# sch_USB3_0.net
KiCad netlist of a schematic drawn in Altium Designer
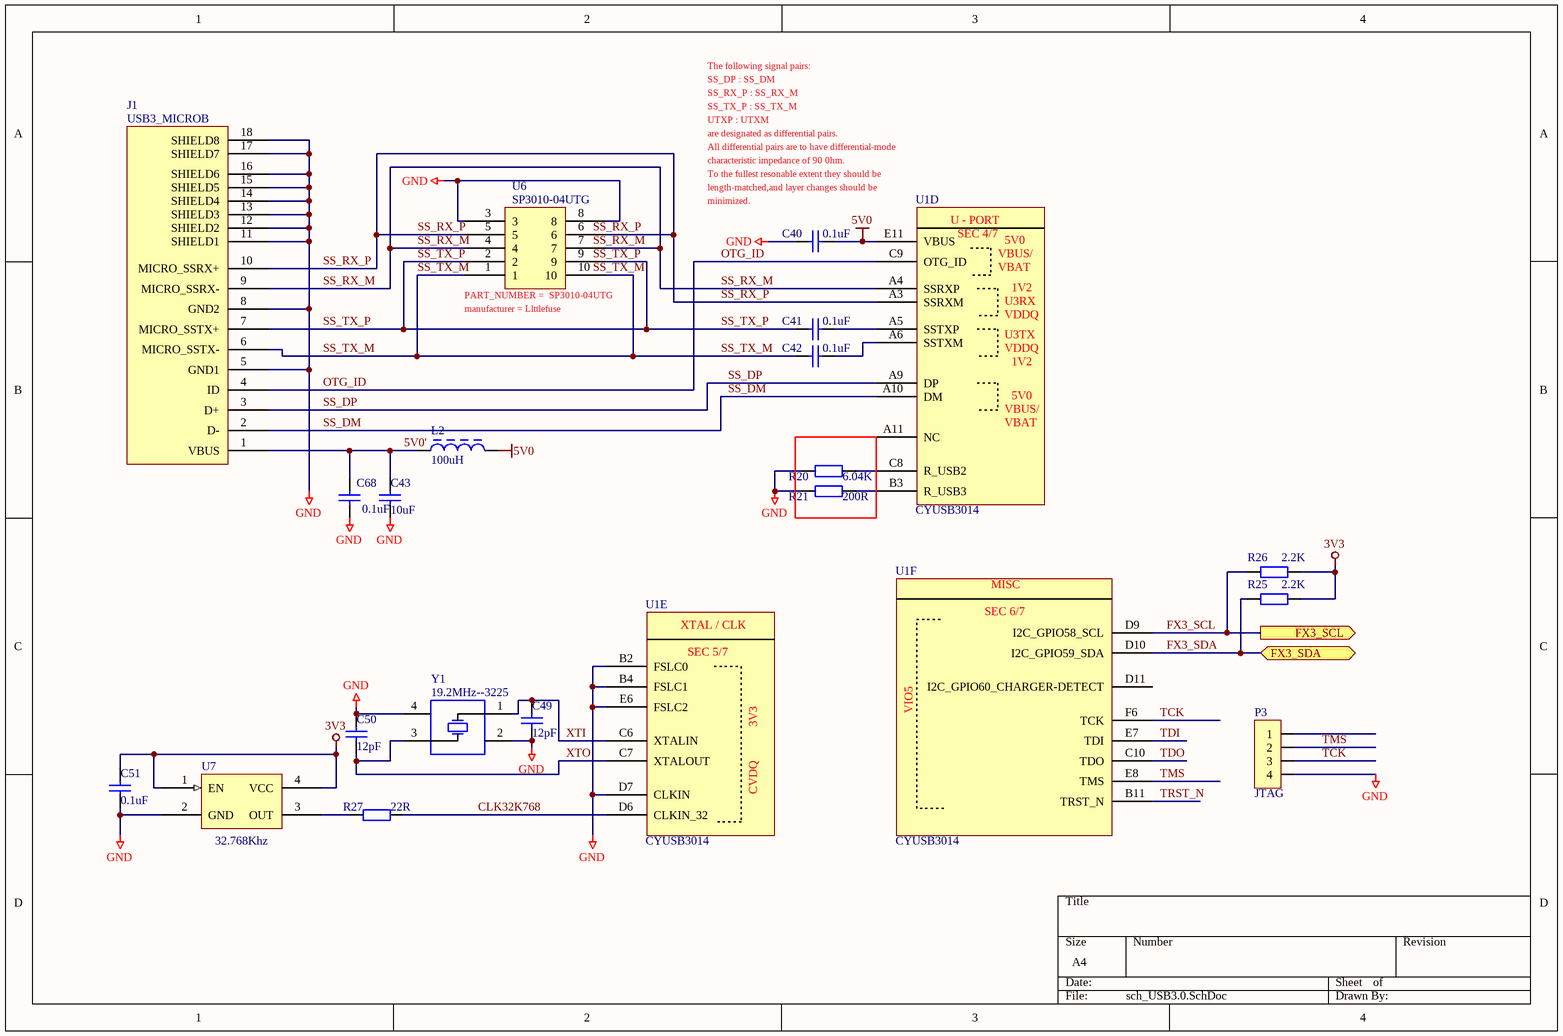
[diagram p0: sch_USB3.0.SchDoc]

(export (version "E")
  (design (tool "Eeschema 10.0.6"))
  (components
    (comp (ref "C40")
      (value "0.1uF")
      (footprint "0402C")
      (description "Capacitor")
      (fields (field (name "PUBLISHER") "Altium Limited"))
      (libsource (lib "Miscellaneous Devices") (part "Cap"))
    )
    (comp (ref "C41")
      (value "0.1uF")
      (footprint "0402C")
      (description "Capacitor")
      (fields (field (name "PUBLISHER") "Altium Limited"))
      (libsource (lib "Miscellaneous Devices") (part "Cap"))
    )
    (comp (ref "C42")
      (value "0.1uF")
      (footprint "0402C")
      (description "Capacitor")
      (fields (field (name "PUBLISHER") "Altium Limited"))
      (libsource (lib "Miscellaneous Devices") (part "Cap"))
    )
    (comp (ref "C43")
      (value "10uF")
      (footprint "0805C")
      (description "Capacitor")
      (fields (field (name "PUBLISHER") "Altium Limited"))
      (libsource (lib "Miscellaneous Devices") (part "Cap"))
    )
    (comp (ref "C49")
      (value "12pF")
      (footprint "0402C")
      (description "Capacitor")
      (fields (field (name "PUBLISHER") "Altium Limited"))
      (libsource (lib "Miscellaneous Devices") (part "Cap"))
    )
    (comp (ref "C50")
      (value "12pF")
      (footprint "0402C")
      (description "Capacitor")
      (fields (field (name "PUBLISHER") "Altium Limited"))
      (libsource (lib "Miscellaneous Devices") (part "Cap"))
    )
    (comp (ref "C51")
      (value "0.1uF")
      (footprint "0402C")
      (description "Capacitor")
      (fields (field (name "PUBLISHER") "Altium Limited"))
      (libsource (lib "Miscellaneous Devices") (part "Cap"))
    )
    (comp (ref "C68")
      (value "0.1uF")
      (footprint "0402C")
      (description "Capacitor")
      (fields (field (name "PUBLISHER") "Altium Limited"))
      (libsource (lib "Miscellaneous Devices") (part "Cap"))
    )
    (comp (ref "J1")
      (value "USB3_MICROB")
      (footprint "USB3_BA_P65L130W51H28")
      (libsource (lib "SZG") (part "USB3_MICROB"))
    )
    (comp (ref "L2")
      (value "100uH")
      (footprint "L_P3D6H9")
      (description "7.2.04.0034 立式电感受10uH 2A")
      (libsource (lib "*") (part "L"))
    )
    (comp (ref "P3")
      (value "JTAG")
      (footprint "WAFER4_P1.25L6.25W3.4H4.3")
      (libsource (lib "KS_Drive") (part "CON4"))
    )
    (comp (ref "R20")
      (value "6.04K")
      (footprint "0402R")
      (description "Resistor")
      (fields (field (name "PUBLISHER") "Altium Limited"))
      (libsource (lib "SZG") (part "Resistor"))
    )
    (comp (ref "R21")
      (value "200R")
      (footprint "0402R")
      (description "Resistor")
      (fields (field (name "PUBLISHER") "Altium Limited"))
      (libsource (lib "SZG") (part "Resistor"))
    )
    (comp (ref "R25")
      (value "2.2K")
      (footprint "0402R")
      (description "Resistor")
      (fields (field (name "PUBLISHER") "Altium Limited"))
      (libsource (lib "SZG") (part "Resistor"))
    )
    (comp (ref "R26")
      (value "2.2K")
      (footprint "0402R")
      (description "Resistor")
      (fields (field (name "PUBLISHER") "Altium Limited"))
      (libsource (lib "SZG") (part "Resistor"))
    )
    (comp (ref "R27")
      (value "22R")
      (footprint "0402R")
      (description "Resistor")
      (fields (field (name "PUBLISHER") "Altium Limited"))
      (libsource (lib "SZG") (part "Resistor"))
    )
    (comp (ref "U1")
      (value "CYUSB3014")
      (footprint "FBGA121_P80L100W100H11")
      (libsource (lib "TXW") (part "CYUSB3014"))
    )
    (comp (ref "U6")
      (value "SP3010-04UTG")
      (footprint "UDFN10_SON_P50L25W10H55")
      (libsource (lib "SZG") (part "SP3010-04UTG"))
    )
    (comp (ref "U7")
      (value "XTAL-3225")
      (footprint "XTAL_3225")
      (libsource (lib "常用晶振器件图SCH") (part "XTAL."))
    )
    (comp (ref "Y1")
      (value "19.2MHz--3225")
      (footprint "XTAL_3225")
      (description "Crystal Oscillator")
      (libsource (lib "常用晶振器件图SCH") (part "XTAL"))
    )
  )
  (nets
    (net (code "1") (name "/5V0'") (class "Default")
      (node (ref "C43") (pin "2") (pinfunction "2_2") (pintype "passive"))
      (node (ref "C68") (pin "1") (pinfunction "1_1") (pintype "passive"))
      (node (ref "J1") (pin "1") (pinfunction "VBUS_1") (pintype "power_in"))
      (node (ref "L2") (pin "1") (pintype "passive"))
    )
    (net (code "2") (name "/CLK32K768") (class "Default")
      (node (ref "R27") (pin "1") (pinfunction "1_1") (pintype "passive"))
      (node (ref "U1") (pin "D6") (pinfunction "CLKIN_32_D6") (pintype "passive"))
    )
    (net (code "3") (name "/FX3_SCL") (class "Default")
      (node (ref "R26") (pin "2") (pinfunction "2_2") (pintype "passive"))
      (node (ref "U1") (pin "D9") (pinfunction "I2C_GPIO58_SCL_D9") (pintype "passive"))
    )
    (net (code "4") (name "/FX3_SDA") (class "Default")
      (node (ref "R25") (pin "2") (pinfunction "2_2") (pintype "passive"))
      (node (ref "U1") (pin "D10") (pinfunction "I2C_GPIO59_SDA_D10") (pintype "passive"))
    )
    (net (code "5") (name "/OTG_ID") (class "Default")
      (node (ref "J1") (pin "4") (pinfunction "ID_4") (pintype "power_in"))
      (node (ref "U1") (pin "C9") (pinfunction "OTG_ID_C9") (pintype "power_in"))
    )
    (net (code "6") (name "/SS_DM") (class "Default")
      (node (ref "J1") (pin "2") (pinfunction "D-_2") (pintype "power_in"))
      (node (ref "U1") (pin "A10") (pinfunction "DM_A10") (pintype "power_in"))
    )
    (net (code "7") (name "/SS_DP") (class "Default")
      (node (ref "J1") (pin "3") (pinfunction "D+_3") (pintype "power_in"))
      (node (ref "U1") (pin "A9") (pinfunction "DP_A9") (pintype "power_in"))
    )
    (net (code "8") (name "/SS_RX_M") (class "Default")
      (node (ref "J1") (pin "9") (pinfunction "MICRO_SSRX-_9") (pintype "power_in"))
      (node (ref "U1") (pin "A4") (pinfunction "SSRXP_A4") (pintype "power_in"))
      (node (ref "U6") (pin "4") (pinfunction "4_4") (pintype "passive"))
      (node (ref "U6") (pin "7") (pinfunction "7_7") (pintype "passive"))
    )
    (net (code "9") (name "/SS_RX_P") (class "Default")
      (node (ref "J1") (pin "10") (pinfunction "MICRO_SSRX+_10") (pintype "power_in"))
      (node (ref "U1") (pin "A3") (pinfunction "SSRXM_A3") (pintype "power_in"))
      (node (ref "U6") (pin "5") (pinfunction "5_5") (pintype "passive"))
      (node (ref "U6") (pin "6") (pinfunction "6_6") (pintype "passive"))
    )
    (net (code "10") (name "/SS_TX_M") (class "Default")
      (node (ref "C42") (pin "2") (pinfunction "2_2") (pintype "passive"))
      (node (ref "J1") (pin "6") (pinfunction "MICRO_SSTX-_6") (pintype "power_in"))
      (node (ref "U6") (pin "1") (pinfunction "1_1") (pintype "passive"))
      (node (ref "U6") (pin "10") (pinfunction "10_10") (pintype "passive"))
    )
    (net (code "11") (name "/SS_TX_P") (class "Default")
      (node (ref "C41") (pin "2") (pinfunction "2_2") (pintype "passive"))
      (node (ref "J1") (pin "7") (pinfunction "MICRO_SSTX+_7") (pintype "power_in"))
      (node (ref "U6") (pin "2") (pinfunction "2_2") (pintype "passive"))
      (node (ref "U6") (pin "9") (pinfunction "9_9") (pintype "passive"))
    )
    (net (code "12") (name "/TCK") (class "Default")
      (node (ref "P3") (pin "3") (pinfunction "3_3") (pintype "passive"))
      (node (ref "U1") (pin "F6") (pinfunction "TCK_F6") (pintype "passive"))
    )
    (net (code "13") (name "/TDI") (class "Default")
      (node (ref "U1") (pin "E7") (pinfunction "TDI_E7") (pintype "passive"))
    )
    (net (code "14") (name "/TDO") (class "Default")
      (node (ref "U1") (pin "C10") (pinfunction "TDO_C10") (pintype "passive"))
    )
    (net (code "15") (name "/TMS") (class "Default")
      (node (ref "P3") (pin "2") (pinfunction "2_2") (pintype "passive"))
      (node (ref "U1") (pin "E8") (pinfunction "TMS_E8") (pintype "passive"))
    )
    (net (code "16") (name "/TRST_N") (class "Default")
      (node (ref "U1") (pin "B11") (pinfunction "TRST_N_B11") (pintype "passive"))
    )
    (net (code "17") (name "/XTI") (class "Default")
      (node (ref "C49") (pin "2") (pinfunction "2_2") (pintype "passive"))
      (node (ref "U1") (pin "C6") (pinfunction "XTALIN_C6") (pintype "passive"))
      (node (ref "Y1") (pin "1") (pinfunction "1_1") (pintype "passive"))
    )
    (net (code "18") (name "/XTO") (class "Default")
      (node (ref "C50") (pin "1") (pinfunction "1_1") (pintype "passive"))
      (node (ref "U1") (pin "C7") (pinfunction "XTALOUT_C7") (pintype "passive"))
      (node (ref "Y1") (pin "3") (pinfunction "3_3") (pintype "passive"))
    )
    (net (code "19") (name "3V3") (class "Default")
      (node (ref "C51") (pin "2") (pinfunction "2_2") (pintype "passive"))
      (node (ref "R25") (pin "1") (pinfunction "1_1") (pintype "passive"))
      (node (ref "R26") (pin "1") (pinfunction "1_1") (pintype "passive"))
      (node (ref "U7") (pin "1") (pinfunction "EN_1") (pintype "input"))
      (node (ref "U7") (pin "4") (pinfunction "VCC_4") (pintype "passive"))
    )
    (net (code "20") (name "5V0") (class "Default")
      (node (ref "C40") (pin "1") (pinfunction "1_1") (pintype "passive"))
      (node (ref "L2") (pin "2") (pintype "passive"))
      (node (ref "U1") (pin "E11") (pinfunction "VBUS_E11") (pintype "power_in"))
    )
    (net (code "21") (name "GND") (class "Default")
      (node (ref "C40") (pin "2") (pinfunction "2_2") (pintype "passive"))
      (node (ref "C43") (pin "1") (pinfunction "1_1") (pintype "passive"))
      (node (ref "C49") (pin "1") (pinfunction "1_1") (pintype "passive"))
      (node (ref "C50") (pin "2") (pinfunction "2_2") (pintype "passive"))
      (node (ref "C51") (pin "1") (pinfunction "1_1") (pintype "passive"))
      (node (ref "C68") (pin "2") (pinfunction "2_2") (pintype "passive"))
      (node (ref "J1") (pin "11") (pinfunction "SHIELD1_11") (pintype "power_in"))
      (node (ref "J1") (pin "12") (pinfunction "SHIELD2_12") (pintype "power_in"))
      (node (ref "J1") (pin "13") (pinfunction "SHIELD3_13") (pintype "power_in"))
      (node (ref "J1") (pin "14") (pinfunction "SHIELD4_14") (pintype "power_in"))
      (node (ref "J1") (pin "15") (pinfunction "SHIELD5_15") (pintype "power_in"))
      (node (ref "J1") (pin "16") (pinfunction "SHIELD6_16") (pintype "power_in"))
      (node (ref "J1") (pin "17") (pinfunction "SHIELD7_17") (pintype "power_in"))
      (node (ref "J1") (pin "18") (pinfunction "SHIELD8_18") (pintype "power_in"))
      (node (ref "J1") (pin "5") (pinfunction "GND1_5") (pintype "power_in"))
      (node (ref "J1") (pin "8") (pinfunction "GND2_8") (pintype "power_in"))
      (node (ref "P3") (pin "4") (pinfunction "4_4") (pintype "passive"))
      (node (ref "R20") (pin "2") (pinfunction "2_2") (pintype "passive"))
      (node (ref "R21") (pin "2") (pinfunction "2_2") (pintype "passive"))
      (node (ref "U1") (pin "B2") (pinfunction "FSLC0_B2") (pintype "passive"))
      (node (ref "U1") (pin "B4") (pinfunction "FSLC1_B4") (pintype "passive"))
      (node (ref "U1") (pin "D7") (pinfunction "CLKIN_D7") (pintype "passive"))
      (node (ref "U1") (pin "E6") (pinfunction "FSLC2_E6") (pintype "passive"))
      (node (ref "U6") (pin "3") (pinfunction "3_3") (pintype "passive"))
      (node (ref "U6") (pin "8") (pinfunction "8_8") (pintype "passive"))
      (node (ref "U7") (pin "2") (pinfunction "GND_2") (pintype "passive"))
      (node (ref "Y1") (pin "2") (pinfunction "2_2") (pintype "passive"))
      (node (ref "Y1") (pin "4") (pinfunction "4_4") (pintype "passive"))
    )
    (net (code "22") (name "Net-(U1D-R_USB2)") (class "Default")
      (node (ref "R20") (pin "1") (pinfunction "1_1") (pintype "passive"))
      (node (ref "U1") (pin "C8") (pinfunction "R_USB2_C8") (pintype "power_in"))
    )
    (net (code "23") (name "Net-(U1D-R_USB3)") (class "Default")
      (node (ref "R21") (pin "1") (pinfunction "1_1") (pintype "passive"))
      (node (ref "U1") (pin "B3") (pinfunction "R_USB3_B3") (pintype "power_in"))
    )
    (net (code "24") (name "Net-(U1D-SSTXM)") (class "Default")
      (node (ref "C42") (pin "1") (pinfunction "1_1") (pintype "passive"))
      (node (ref "U1") (pin "A6") (pinfunction "SSTXM_A6") (pintype "power_in"))
    )
    (net (code "25") (name "Net-(U1D-SSTXP)") (class "Default")
      (node (ref "C41") (pin "1") (pinfunction "1_1") (pintype "passive"))
      (node (ref "U1") (pin "A5") (pinfunction "SSTXP_A5") (pintype "power_in"))
    )
    (net (code "26") (name "Net-(U7-OUT)") (class "Default")
      (node (ref "R27") (pin "2") (pinfunction "2_2") (pintype "passive"))
      (node (ref "U7") (pin "3") (pinfunction "OUT_3") (pintype "passive"))
    )
    (net (code "27") (name "unconnected-(P3-Pad1)") (class "Default")
      (node (ref "P3") (pin "1") (pinfunction "1_1") (pintype "passive"))
    )
    (net (code "28") (name "unconnected-(U1D-NC-PadA11)") (class "Default")
      (node (ref "U1") (pin "A11") (pinfunction "NC_A11") (pintype "power_in"))
    )
    (net (code "29") (name "unconnected-(U1F-I2C_GPIO60_CHARGER-DETECT-PadD11)") (class "Default")
      (node (ref "U1") (pin "D11") (pinfunction "I2C_GPIO60_CHARGER-DETECT_D11") (pintype "passive"))
    )
  )
)
